# PUS_Decoupling.net
KiCad netlist of a schematic drawn in Altium Designer
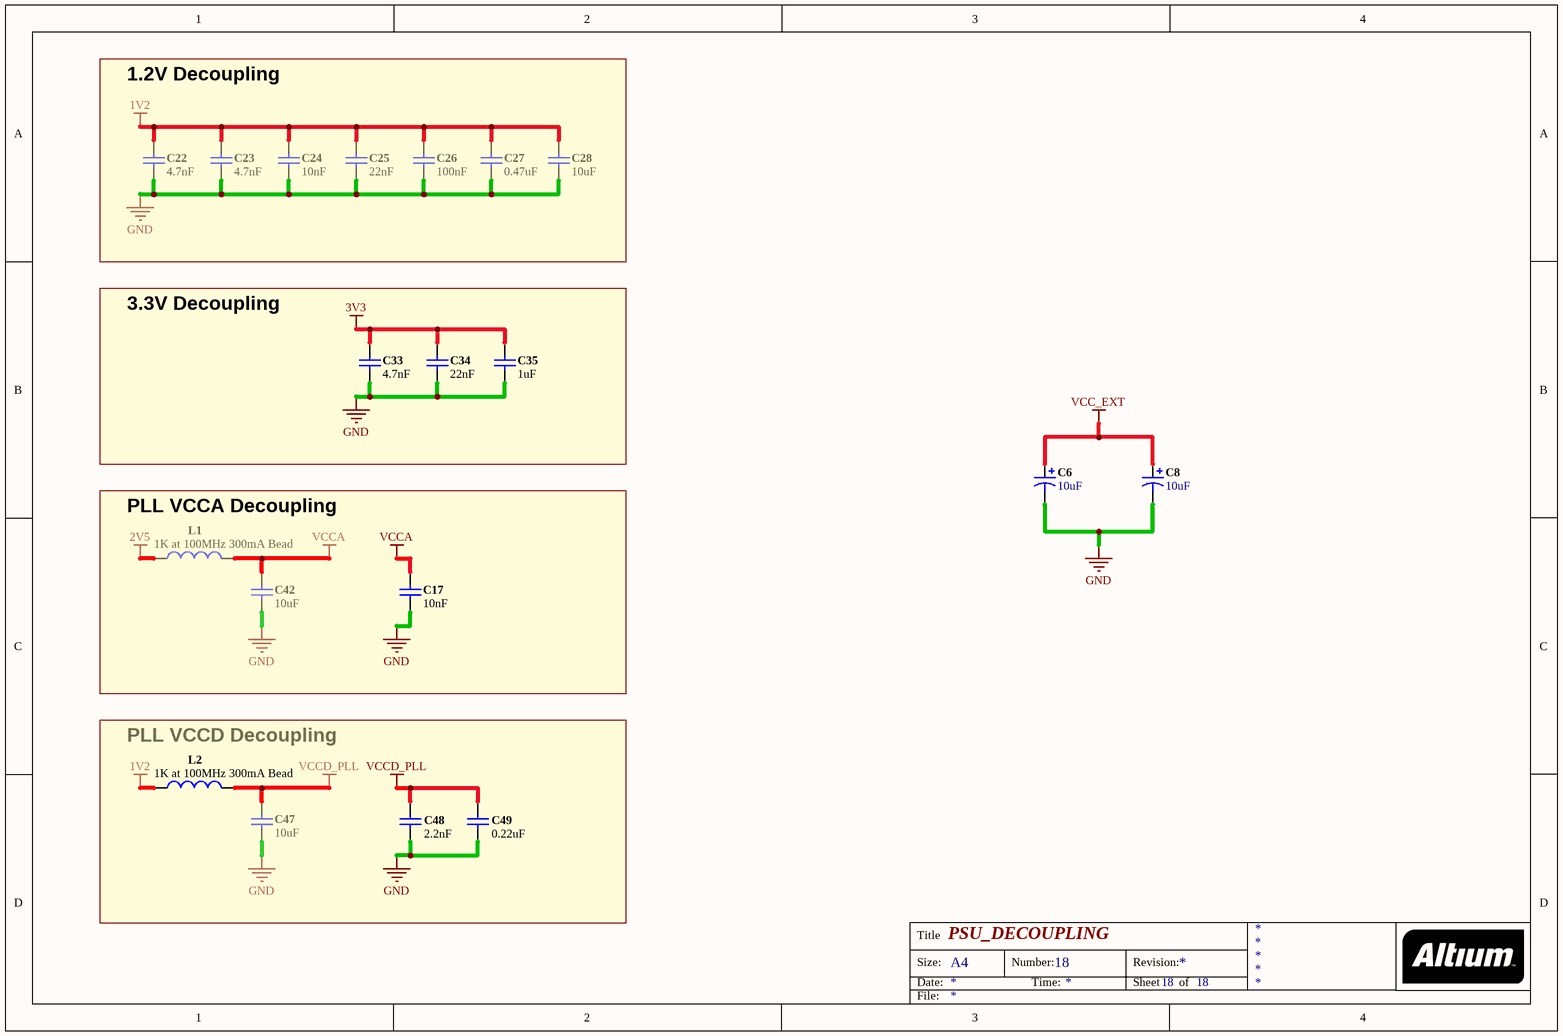
[diagram p0: PUS_Decoupling.SchDoc]

(export (version "E")
  (design (tool "Eeschema 10.0.6"))
  (components
    (comp (ref "C6")
      (value "10uF")
      (footprint "AVX-CAPC3528_V")
      (description "Capacitor, Tantalum, 10uF 10% 20V MCCT-B (3528)")
      (fields (field (name "PARTNUMBER") "TAJB106K020RNJ") (field (name "MANUFACTURER") "AVX"))
      (libsource (lib "Arduino - FPGA Development Board") (part "CMP-0279-00001-1"))
    )
    (comp (ref "C8")
      (value "10uF")
      (footprint "AVX-CAPC3528_V")
      (description "Capacitor, Tantalum, 10uF 10% 20V MCCT-B (3528)")
      (fields (field (name "PARTNUMBER") "TAJB106K020RNJ") (field (name "MANUFACTURER") "AVX"))
      (libsource (lib "Arduino - FPGA Development Board") (part "CMP-0279-00001-1"))
    )
    (comp (ref "C17")
      (value "10nF")
      (footprint "0603C-GENERIC")
      (description "Capacitor, Ceramic, 10% 10V 0603 X7R")
      (fields (field (name "TOLERANCE") "±10%"))
      (libsource (lib "Component_Database") (part "CAP_NP"))
    )
    (comp (ref "C22")
      (value "4.7nF")
      (footprint "0603C-GENERIC")
      (description "Capacitor, Ceramic, 10% 10V 0603 X7R")
      (fields (field (name "TOLERANCE") "±10%"))
      (libsource (lib "Component_Database") (part "CAP_NP"))
    )
    (comp (ref "C23")
      (value "4.7nF")
      (footprint "0603C-GENERIC")
      (description "Capacitor, Ceramic, 10% 10V 0603 X7R")
      (fields (field (name "TOLERANCE") "±10%"))
      (libsource (lib "Component_Database") (part "CAP_NP"))
    )
    (comp (ref "C24")
      (value "10nF")
      (footprint "0603C-GENERIC")
      (description "Capacitor, Ceramic, 10% 10V 0603 X7R")
      (fields (field (name "TOLERANCE") "±10%"))
      (libsource (lib "Component_Database") (part "CAP_NP"))
    )
    (comp (ref "C25")
      (value "22nF")
      (footprint "0603C-GENERIC")
      (description "Capacitor, Ceramic, 10% 10V 0603 X7R")
      (fields (field (name "TOLERANCE") "±10%"))
      (libsource (lib "Component_Database") (part "CAP_NP"))
    )
    (comp (ref "C26")
      (value "100nF")
      (footprint "0603C-GENERIC")
      (description "Capacitor, Ceramic, 10% 10V 0603 X7R")
      (fields (field (name "TOLERANCE") "±10%"))
      (libsource (lib "Component_Database") (part "CAP_NP"))
    )
    (comp (ref "C27")
      (value "0.47uF")
      (footprint "0603C-GENERIC")
      (description "Capacitor, Ceramic, 10% 10V 0603 X7R")
      (fields (field (name "TOLERANCE") "±10%"))
      (libsource (lib "Component_Database") (part "CAP_NP"))
    )
    (comp (ref "C28")
      (value "10uF")
      (footprint "0603C-GENERIC")
      (description "Capacitor, Ceramic, 10% 10V 0603 X7R")
      (fields (field (name "TOLERANCE") "±10%"))
      (libsource (lib "Component_Database") (part "CAP_NP"))
    )
    (comp (ref "C33")
      (value "4.7nF")
      (footprint "0603C-GENERIC")
      (description "Capacitor, Ceramic, 10% 10V 0603 X7R")
      (fields (field (name "TOLERANCE") "±10%"))
      (libsource (lib "Component_Database") (part "CAP_NP"))
    )
    (comp (ref "C34")
      (value "22nF")
      (footprint "0603C-GENERIC")
      (description "Capacitor, Ceramic, 10% 10V 0603 X7R")
      (fields (field (name "TOLERANCE") "±10%"))
      (libsource (lib "Component_Database") (part "CAP_NP"))
    )
    (comp (ref "C35")
      (value "1uF")
      (footprint "0603C-GENERIC")
      (description "Capacitor, Ceramic, 10% 10V 0603 X7R")
      (fields (field (name "TOLERANCE") "±10%"))
      (libsource (lib "Component_Database") (part "CAP_NP"))
    )
    (comp (ref "C42")
      (value "10uF")
      (footprint "0805C-GENERIC")
      (description "Capacitor, Ceramic, 10% 10V 0805 X7R")
      (fields (field (name "TOLERANCE") "±10%"))
      (libsource (lib "Component_Database") (part "CAP_NP"))
    )
    (comp (ref "C47")
      (value "10uF")
      (footprint "0805C-GENERIC")
      (description "Capacitor, Ceramic, 10% 10V 0805 X7R")
      (fields (field (name "TOLERANCE") "±10%"))
      (libsource (lib "Component_Database") (part "CAP_NP"))
    )
    (comp (ref "C48")
      (value "2.2nF")
      (footprint "0603C-GENERIC")
      (description "Capacitor, Ceramic, 10% 10V 0603 X7R")
      (fields (field (name "TOLERANCE") "±10%"))
      (libsource (lib "Component_Database") (part "CAP_NP"))
    )
    (comp (ref "C49")
      (value "0.22uF")
      (footprint "0603C-GENERIC")
      (description "Capacitor, Ceramic, 10% 10V 0603 X7R")
      (fields (field (name "TOLERANCE") "±10%"))
      (libsource (lib "Component_Database") (part "CAP_NP"))
    )
    (comp (ref "L1")
      (value "1K at 100MHz 300mA Bead")
      (footprint "0805FB-1KZ")
      (description "Inductor, Ferrite Bead 1K@100MHz 300mA 0805 BK1005HS102-T")
      (libsource (lib "AltiumDesignLibrary") (part "IND-FER"))
    )
    (comp (ref "L2")
      (value "1K at 100MHz 300mA Bead")
      (footprint "0805FB-1KZ")
      (description "Inductor, Ferrite Bead 1K@100MHz 300mA 0805 BK1005HS102-T")
      (libsource (lib "AltiumDesignLibrary") (part "IND-FER"))
    )
  )
  (nets
    (net (code "1") (name "1V2") (class "Default")
      (node (ref "C22") (pin "1") (pinfunction "1_1") (pintype "passive"))
      (node (ref "C23") (pin "1") (pinfunction "1_1") (pintype "passive"))
      (node (ref "C24") (pin "1") (pinfunction "1_1") (pintype "passive"))
      (node (ref "C25") (pin "1") (pinfunction "1_1") (pintype "passive"))
      (node (ref "C26") (pin "1") (pinfunction "1_1") (pintype "passive"))
      (node (ref "C27") (pin "1") (pinfunction "1_1") (pintype "passive"))
      (node (ref "C28") (pin "1") (pinfunction "1_1") (pintype "passive"))
      (node (ref "L2") (pin "1") (pinfunction "1_1") (pintype "passive"))
    )
    (net (code "2") (name "2V5") (class "Default")
      (node (ref "L1") (pin "1") (pinfunction "1_1") (pintype "passive"))
    )
    (net (code "3") (name "3V3") (class "Default")
      (node (ref "C33") (pin "1") (pinfunction "1_1") (pintype "passive"))
      (node (ref "C34") (pin "1") (pinfunction "1_1") (pintype "passive"))
      (node (ref "C35") (pin "1") (pinfunction "1_1") (pintype "passive"))
    )
    (net (code "4") (name "GND") (class "Default")
      (node (ref "C17") (pin "1") (pinfunction "1_1") (pintype "passive"))
      (node (ref "C22") (pin "2") (pinfunction "2_2") (pintype "passive"))
      (node (ref "C23") (pin "2") (pinfunction "2_2") (pintype "passive"))
      (node (ref "C24") (pin "2") (pinfunction "2_2") (pintype "passive"))
      (node (ref "C25") (pin "2") (pinfunction "2_2") (pintype "passive"))
      (node (ref "C26") (pin "2") (pinfunction "2_2") (pintype "passive"))
      (node (ref "C27") (pin "2") (pinfunction "2_2") (pintype "passive"))
      (node (ref "C28") (pin "2") (pinfunction "2_2") (pintype "passive"))
      (node (ref "C33") (pin "2") (pinfunction "2_2") (pintype "passive"))
      (node (ref "C34") (pin "2") (pinfunction "2_2") (pintype "passive"))
      (node (ref "C35") (pin "2") (pinfunction "2_2") (pintype "passive"))
      (node (ref "C42") (pin "1") (pinfunction "1_1") (pintype "passive"))
      (node (ref "C47") (pin "1") (pinfunction "1_1") (pintype "passive"))
      (node (ref "C48") (pin "2") (pinfunction "2_2") (pintype "passive"))
      (node (ref "C49") (pin "2") (pinfunction "2_2") (pintype "passive"))
      (node (ref "C6") (pin "2") (pinfunction "2_2") (pintype "passive"))
      (node (ref "C8") (pin "2") (pinfunction "2_2") (pintype "passive"))
    )
    (net (code "5") (name "VCCA") (class "Default")
      (node (ref "C17") (pin "2") (pinfunction "2_2") (pintype "passive"))
      (node (ref "C42") (pin "2") (pinfunction "2_2") (pintype "passive"))
      (node (ref "L1") (pin "2") (pinfunction "2_2") (pintype "passive"))
    )
    (net (code "6") (name "VCCD_PLL") (class "Default")
      (node (ref "C47") (pin "2") (pinfunction "2_2") (pintype "passive"))
      (node (ref "C48") (pin "1") (pinfunction "1_1") (pintype "passive"))
      (node (ref "C49") (pin "1") (pinfunction "1_1") (pintype "passive"))
      (node (ref "L2") (pin "2") (pinfunction "2_2") (pintype "passive"))
    )
    (net (code "7") (name "VCC_EXT") (class "Default")
      (node (ref "C6") (pin "1") (pinfunction "1_1") (pintype "passive"))
      (node (ref "C8") (pin "1") (pinfunction "1_1") (pintype "passive"))
    )
  )
)
